# MxxxOVR.net
KiCad netlist of a schematic drawn in EAGLE
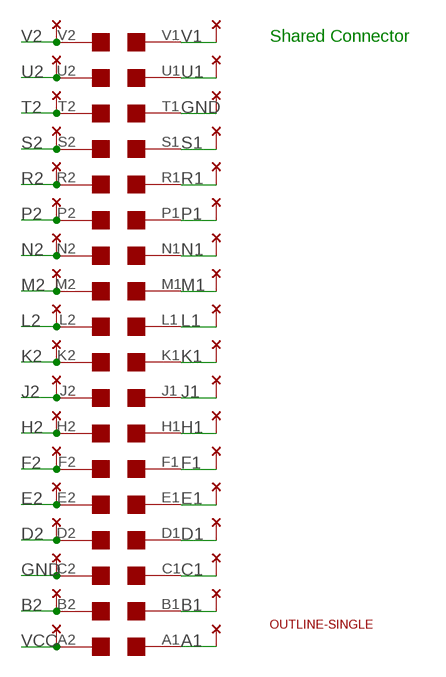
[diagram p0: schematic, sheet 1]
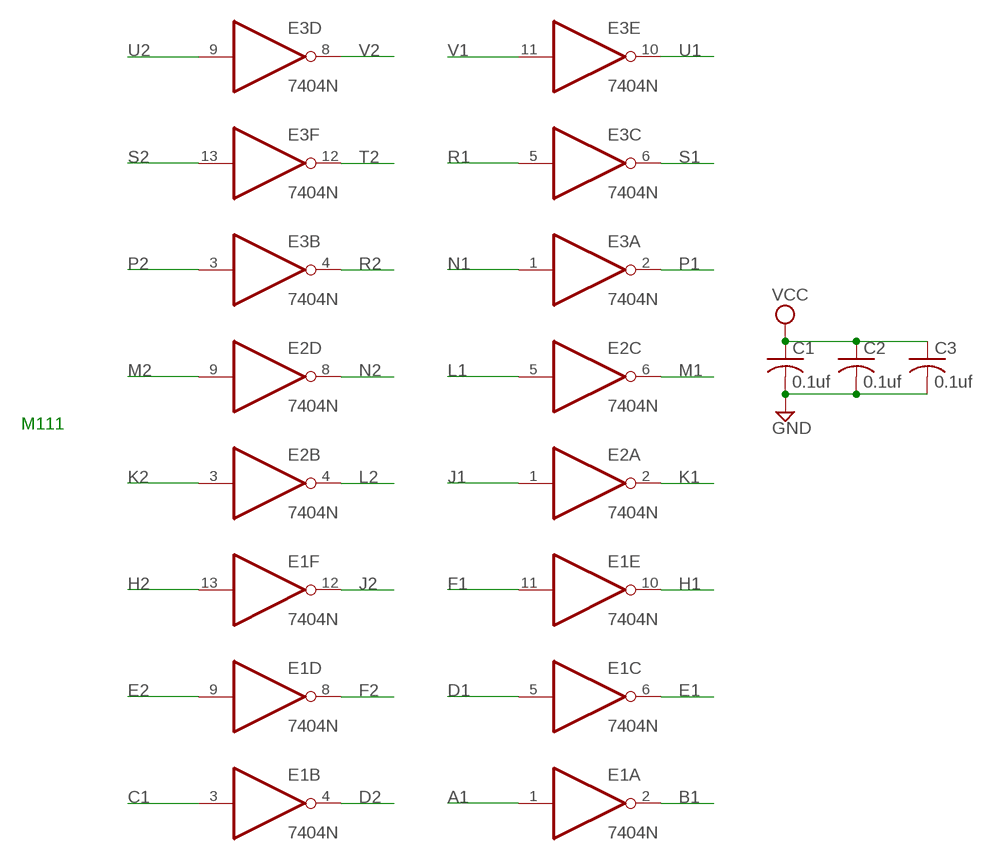
[diagram p1: schematic, sheet 2]
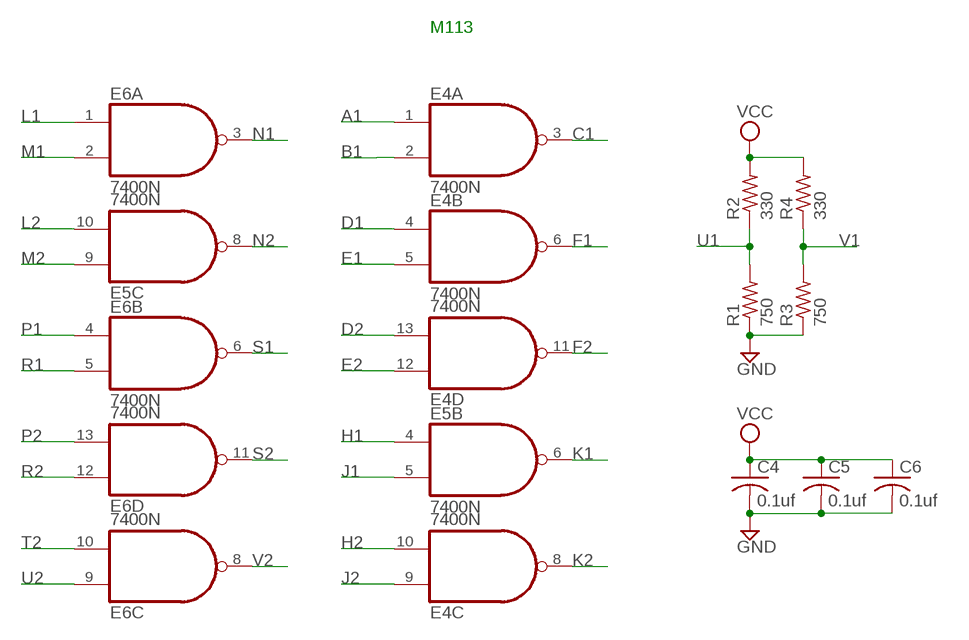
[diagram p2: schematic, sheet 3]
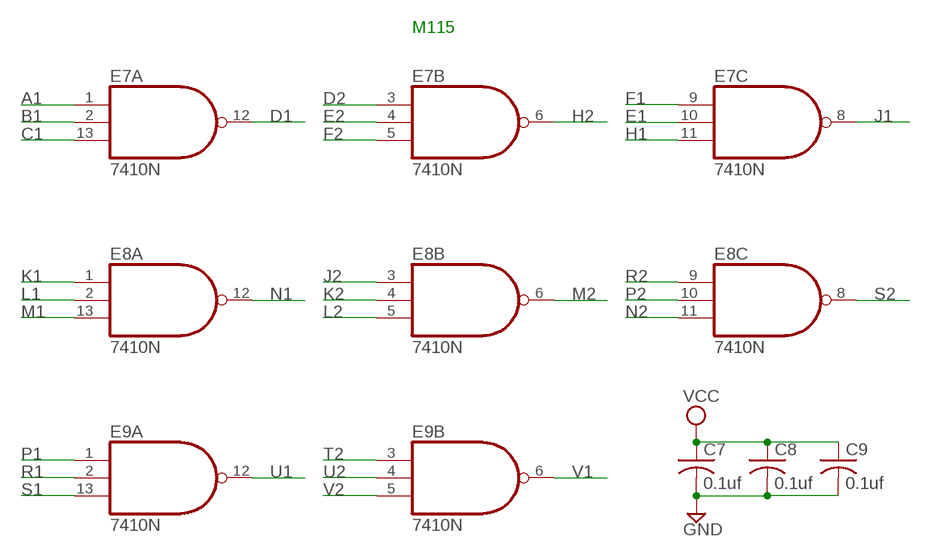
[diagram p3: schematic, sheet 4]
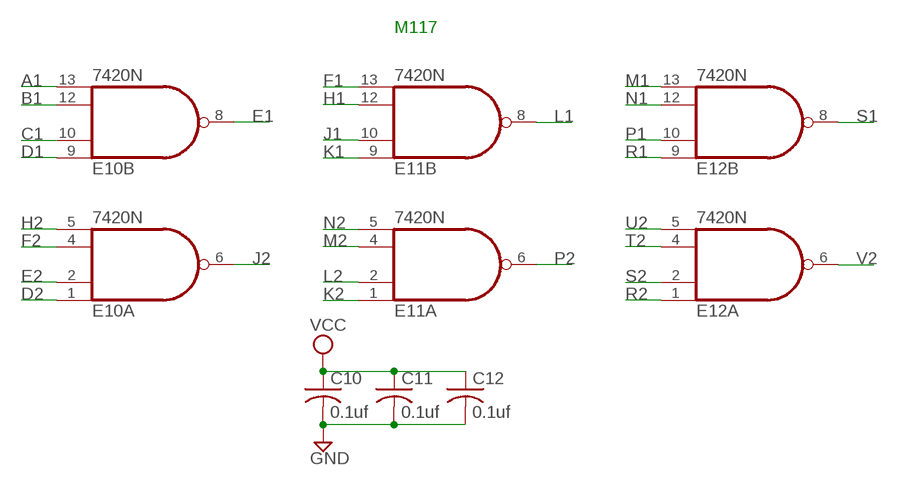
[diagram p4: schematic, sheet 5]
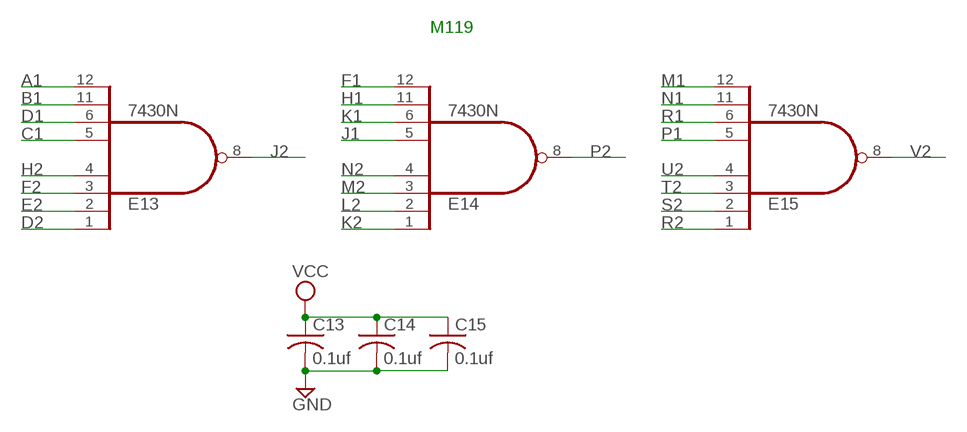
[diagram p5: schematic, sheet 6]

(export (version "E")
  (design (tool "Eeschema 10.0.6"))
  (components
    (comp (ref "C4")
      (value "0.1uf")
      (footprint "eagle-import:C050-025X075")
      (libsource (lib "eagle-import") (part "C-US050-025X075"))
    )
    (comp (ref "C5")
      (value "0.1uf")
      (footprint "eagle-import:C050-025X075")
      (libsource (lib "eagle-import") (part "C-US050-025X075"))
    )
    (comp (ref "C6")
      (value "0.1uf")
      (footprint "eagle-import:C050-025X075")
      (libsource (lib "eagle-import") (part "C-US050-025X075"))
    )
    (comp (ref "E4")
      (value "7400N")
      (footprint "eagle-import:DIL14")
      (libsource (lib "eagle-import") (part "7400N"))
    )
    (comp (ref "E5")
      (value "7400N")
      (footprint "eagle-import:DIL14")
      (libsource (lib "eagle-import") (part "7400N"))
    )
    (comp (ref "E6")
      (value "7400N")
      (footprint "eagle-import:DIL14")
      (libsource (lib "eagle-import") (part "7400N"))
    )
    (comp (ref "R1")
      (value "750")
      (footprint "eagle-import:0207_10")
      (libsource (lib "eagle-import") (part "R-US_0207/10"))
    )
    (comp (ref "R2")
      (value "330")
      (footprint "eagle-import:0207_10")
      (libsource (lib "eagle-import") (part "R-US_0207/10"))
    )
    (comp (ref "R3")
      (value "750")
      (footprint "eagle-import:0207_10")
      (libsource (lib "eagle-import") (part "R-US_0207/10"))
    )
    (comp (ref "R4")
      (value "330")
      (footprint "eagle-import:0207_10")
      (libsource (lib "eagle-import") (part "R-US_0207/10"))
    )
    (comp (ref "U$1")
      (value "EDGE-2CONNECTOR")
      (footprint "eagle-import:EDGE-CON2")
      (libsource (lib "eagle-import") (part "EDGE-2CONNECTOR"))
    )
    (comp (ref "U$4")
      (value "THRU-HOLE2A")
      (footprint "eagle-import:THRU-HOLEA")
      (libsource (lib "eagle-import") (part "THRU-HOLE2A"))
    )
    (comp (ref "U$5")
      (value "OUTLINE-SINGLE")
      (footprint "eagle-import:SINGLE")
      (libsource (lib "eagle-import") (part "OUTLINE-SINGLE"))
    )
    (comp (ref "C13")
      (value "0.1uf")
      (footprint "eagle-import:C050-025X075")
      (libsource (lib "eagle-import") (part "C-US050-025X075"))
    )
    (comp (ref "C14")
      (value "0.1uf")
      (footprint "eagle-import:C050-025X075")
      (libsource (lib "eagle-import") (part "C-US050-025X075"))
    )
    (comp (ref "C15")
      (value "0.1uf")
      (footprint "eagle-import:C050-025X075")
      (libsource (lib "eagle-import") (part "C-US050-025X075"))
    )
    (comp (ref "E13")
      (value "7430N")
      (footprint "eagle-import:DIL14")
      (libsource (lib "eagle-import") (part "7430N"))
    )
    (comp (ref "E14")
      (value "7430N")
      (footprint "eagle-import:DIL14")
      (libsource (lib "eagle-import") (part "7430N"))
    )
    (comp (ref "E15")
      (value "7430N")
      (footprint "eagle-import:DIL14")
      (libsource (lib "eagle-import") (part "7430N"))
    )
    (comp (ref "C1")
      (value "0.1uf")
      (footprint "eagle-import:C050-025X075")
      (libsource (lib "eagle-import") (part "C-US050-025X075"))
    )
    (comp (ref "C2")
      (value "0.1uf")
      (footprint "eagle-import:C050-025X075")
      (libsource (lib "eagle-import") (part "C-US050-025X075"))
    )
    (comp (ref "C3")
      (value "0.1uf")
      (footprint "eagle-import:C050-025X075")
      (libsource (lib "eagle-import") (part "C-US050-025X075"))
    )
    (comp (ref "E1")
      (value "7404N")
      (footprint "eagle-import:DIL14")
      (libsource (lib "eagle-import") (part "7404N"))
    )
    (comp (ref "E2")
      (value "7404N")
      (footprint "eagle-import:DIL14")
      (libsource (lib "eagle-import") (part "7404N"))
    )
    (comp (ref "E3")
      (value "7404N")
      (footprint "eagle-import:DIL14")
      (libsource (lib "eagle-import") (part "7404N"))
    )
    (comp (ref "C10")
      (value "0.1uf")
      (footprint "eagle-import:C050-025X075")
      (libsource (lib "eagle-import") (part "C-US050-025X075"))
    )
    (comp (ref "C11")
      (value "0.1uf")
      (footprint "eagle-import:C050-025X075")
      (libsource (lib "eagle-import") (part "C-US050-025X075"))
    )
    (comp (ref "C12")
      (value "0.1uf")
      (footprint "eagle-import:C050-025X075")
      (libsource (lib "eagle-import") (part "C-US050-025X075"))
    )
    (comp (ref "E10")
      (value "7420N")
      (footprint "eagle-import:DIL14")
      (libsource (lib "eagle-import") (part "7420NS"))
    )
    (comp (ref "E11")
      (value "7420N")
      (footprint "eagle-import:DIL14")
      (libsource (lib "eagle-import") (part "7420NS"))
    )
    (comp (ref "E12")
      (value "7420N")
      (footprint "eagle-import:DIL14")
      (libsource (lib "eagle-import") (part "7420NS"))
    )
    (comp (ref "C7")
      (value "0.1uf")
      (footprint "eagle-import:C050-025X075")
      (libsource (lib "eagle-import") (part "C-US050-025X075"))
    )
    (comp (ref "C8")
      (value "0.1uf")
      (footprint "eagle-import:C050-025X075")
      (libsource (lib "eagle-import") (part "C-US050-025X075"))
    )
    (comp (ref "C9")
      (value "0.1uf")
      (footprint "eagle-import:C050-025X075")
      (libsource (lib "eagle-import") (part "C-US050-025X075"))
    )
    (comp (ref "E7")
      (value "7410N")
      (footprint "eagle-import:DIL14")
      (libsource (lib "eagle-import") (part "7410N"))
    )
    (comp (ref "E8")
      (value "7410N")
      (footprint "eagle-import:DIL14")
      (libsource (lib "eagle-import") (part "7410N"))
    )
    (comp (ref "E9")
      (value "7410N")
      (footprint "eagle-import:DIL14")
      (libsource (lib "eagle-import") (part "7410N"))
    )
  )
  (nets
    (net (code "1") (name "A1") (class "Default")
      (node (ref "E1") (pin "1") (pinfunction "I_1") (pintype "input"))
      (node (ref "E10") (pin "13") (pinfunction "I3_13") (pintype "input"))
      (node (ref "E13") (pin "12") (pinfunction "I7_12") (pintype "input"))
      (node (ref "E4") (pin "1") (pinfunction "I0_1") (pintype "input"))
      (node (ref "E7") (pin "1") (pinfunction "I0_1") (pintype "input"))
      (node (ref "U$1") (pin "A1") (pinfunction "1_A1") (pintype "bidirectional"))
      (node (ref "U$4") (pin "A1") (pinfunction "P$1_A1") (pintype "passive"))
    )
    (net (code "2") (name "B1") (class "Default")
      (node (ref "E1") (pin "2") (pinfunction "O_2") (pintype "output"))
      (node (ref "E10") (pin "12") (pinfunction "I2_12") (pintype "input"))
      (node (ref "E13") (pin "11") (pinfunction "I6_11") (pintype "input"))
      (node (ref "E4") (pin "2") (pinfunction "I1_2") (pintype "input"))
      (node (ref "E7") (pin "2") (pinfunction "I1_2") (pintype "input"))
      (node (ref "U$1") (pin "B1") (pinfunction "1_B1") (pintype "bidirectional"))
      (node (ref "U$4") (pin "B1") (pinfunction "P$1_B1") (pintype "passive"))
    )
    (net (code "3") (name "B2") (class "Default")
      (node (ref "U$1") (pin "B2") (pinfunction "1_B2") (pintype "bidirectional"))
      (node (ref "U$4") (pin "B2") (pinfunction "P$1_B2") (pintype "passive"))
    )
    (net (code "4") (name "C1") (class "Default")
      (node (ref "E1") (pin "3") (pinfunction "I_3") (pintype "input"))
      (node (ref "E10") (pin "10") (pinfunction "I1_10") (pintype "input"))
      (node (ref "E13") (pin "5") (pinfunction "I4_5") (pintype "input"))
      (node (ref "E4") (pin "3") (pinfunction "O_3") (pintype "output"))
      (node (ref "E7") (pin "13") (pinfunction "I2_13") (pintype "input"))
      (node (ref "U$1") (pin "C1") (pinfunction "1_C1") (pintype "bidirectional"))
      (node (ref "U$4") (pin "C1") (pinfunction "P$1_C1") (pintype "passive"))
    )
    (net (code "5") (name "D1") (class "Default")
      (node (ref "E1") (pin "5") (pinfunction "I_5") (pintype "input"))
      (node (ref "E10") (pin "9") (pinfunction "I0_9") (pintype "input"))
      (node (ref "E13") (pin "6") (pinfunction "I5_6") (pintype "input"))
      (node (ref "E4") (pin "4") (pinfunction "I0_4") (pintype "input"))
      (node (ref "E7") (pin "12") (pinfunction "O_12") (pintype "output"))
      (node (ref "U$1") (pin "D1") (pinfunction "1_D1") (pintype "bidirectional"))
      (node (ref "U$4") (pin "D1") (pinfunction "P$1_D1") (pintype "passive"))
    )
    (net (code "6") (name "D2") (class "Default")
      (node (ref "E1") (pin "4") (pinfunction "O_4") (pintype "output"))
      (node (ref "E10") (pin "1") (pinfunction "I0_1") (pintype "input"))
      (node (ref "E13") (pin "1") (pinfunction "I0_1") (pintype "input"))
      (node (ref "E4") (pin "13") (pinfunction "I1_13") (pintype "input"))
      (node (ref "E7") (pin "3") (pinfunction "I0_3") (pintype "input"))
      (node (ref "U$1") (pin "D2") (pinfunction "1_D2") (pintype "bidirectional"))
      (node (ref "U$4") (pin "D2") (pinfunction "P$1_D2") (pintype "passive"))
    )
    (net (code "7") (name "E1") (class "Default")
      (node (ref "E1") (pin "6") (pinfunction "O_6") (pintype "output"))
      (node (ref "E10") (pin "8") (pinfunction "O_8") (pintype "output"))
      (node (ref "E4") (pin "5") (pinfunction "I1_5") (pintype "input"))
      (node (ref "E7") (pin "10") (pinfunction "I1_10") (pintype "input"))
      (node (ref "U$1") (pin "E1") (pinfunction "1_E1") (pintype "bidirectional"))
      (node (ref "U$4") (pin "E1") (pinfunction "P$1_E1") (pintype "passive"))
    )
    (net (code "8") (name "E2") (class "Default")
      (node (ref "E1") (pin "9") (pinfunction "I_9") (pintype "input"))
      (node (ref "E10") (pin "2") (pinfunction "I1_2") (pintype "input"))
      (node (ref "E13") (pin "2") (pinfunction "I1_2") (pintype "input"))
      (node (ref "E4") (pin "12") (pinfunction "I0_12") (pintype "input"))
      (node (ref "E7") (pin "4") (pinfunction "I1_4") (pintype "input"))
      (node (ref "U$1") (pin "E2") (pinfunction "1_E2") (pintype "bidirectional"))
      (node (ref "U$4") (pin "E2") (pinfunction "P$1_E2") (pintype "passive"))
    )
    (net (code "9") (name "F1") (class "Default")
      (node (ref "E1") (pin "11") (pinfunction "I_11") (pintype "input"))
      (node (ref "E11") (pin "13") (pinfunction "I3_13") (pintype "input"))
      (node (ref "E14") (pin "12") (pinfunction "I7_12") (pintype "input"))
      (node (ref "E4") (pin "6") (pinfunction "O_6") (pintype "output"))
      (node (ref "E7") (pin "9") (pinfunction "I0_9") (pintype "input"))
      (node (ref "U$1") (pin "F1") (pinfunction "1_F1") (pintype "bidirectional"))
      (node (ref "U$4") (pin "F1") (pinfunction "P$1_F1") (pintype "passive"))
    )
    (net (code "10") (name "F2") (class "Default")
      (node (ref "E1") (pin "8") (pinfunction "O_8") (pintype "output"))
      (node (ref "E10") (pin "4") (pinfunction "I2_4") (pintype "input"))
      (node (ref "E13") (pin "3") (pinfunction "I2_3") (pintype "input"))
      (node (ref "E4") (pin "11") (pinfunction "O_11") (pintype "output"))
      (node (ref "E7") (pin "5") (pinfunction "I2_5") (pintype "input"))
      (node (ref "U$1") (pin "F2") (pinfunction "1_F2") (pintype "bidirectional"))
      (node (ref "U$4") (pin "F2") (pinfunction "P$1_F2") (pintype "passive"))
    )
    (net (code "11") (name "GND") (class "Default")
      (node (ref "C1") (pin "2") (pinfunction "2_2") (pintype "passive"))
      (node (ref "C10") (pin "2") (pinfunction "2_2") (pintype "passive"))
      (node (ref "C11") (pin "2") (pinfunction "2_2") (pintype "passive"))
      (node (ref "C12") (pin "2") (pinfunction "2_2") (pintype "passive"))
      (node (ref "C13") (pin "2") (pinfunction "2_2") (pintype "passive"))
      (node (ref "C14") (pin "2") (pinfunction "2_2") (pintype "passive"))
      (node (ref "C15") (pin "2") (pinfunction "2_2") (pintype "passive"))
      (node (ref "C2") (pin "2") (pinfunction "2_2") (pintype "passive"))
      (node (ref "C3") (pin "2") (pinfunction "2_2") (pintype "passive"))
      (node (ref "C4") (pin "2") (pinfunction "2_2") (pintype "passive"))
      (node (ref "C5") (pin "2") (pinfunction "2_2") (pintype "passive"))
      (node (ref "C6") (pin "2") (pinfunction "2_2") (pintype "passive"))
      (node (ref "C7") (pin "2") (pinfunction "2_2") (pintype "passive"))
      (node (ref "C8") (pin "2") (pinfunction "2_2") (pintype "passive"))
      (node (ref "C9") (pin "2") (pinfunction "2_2") (pintype "passive"))
      (node (ref "R1") (pin "1") (pinfunction "1_1") (pintype "passive"))
      (node (ref "R3") (pin "1") (pinfunction "1_1") (pintype "passive"))
      (node (ref "U$1") (pin "C2") (pinfunction "1_C2") (pintype "bidirectional"))
      (node (ref "U$1") (pin "T1") (pinfunction "1_T1") (pintype "bidirectional"))
      (node (ref "U$4") (pin "C2") (pinfunction "P$1_C2") (pintype "passive"))
      (node (ref "U$4") (pin "T1") (pinfunction "P$1_T1") (pintype "passive"))
    )
    (net (code "12") (name "H1") (class "Default")
      (node (ref "E1") (pin "10") (pinfunction "O_10") (pintype "output"))
      (node (ref "E11") (pin "12") (pinfunction "I2_12") (pintype "input"))
      (node (ref "E14") (pin "11") (pinfunction "I6_11") (pintype "input"))
      (node (ref "E5") (pin "4") (pinfunction "I0_4") (pintype "input"))
      (node (ref "E7") (pin "11") (pinfunction "I2_11") (pintype "input"))
      (node (ref "U$1") (pin "H1") (pinfunction "1_H1") (pintype "bidirectional"))
      (node (ref "U$4") (pin "H1") (pinfunction "P$1_H1") (pintype "passive"))
    )
    (net (code "13") (name "H2") (class "Default")
      (node (ref "E1") (pin "13") (pinfunction "I_13") (pintype "input"))
      (node (ref "E10") (pin "5") (pinfunction "I3_5") (pintype "input"))
      (node (ref "E13") (pin "4") (pinfunction "I3_4") (pintype "input"))
      (node (ref "E4") (pin "10") (pinfunction "I1_10") (pintype "input"))
      (node (ref "E7") (pin "6") (pinfunction "O_6") (pintype "output"))
      (node (ref "U$1") (pin "H2") (pinfunction "1_H2") (pintype "bidirectional"))
      (node (ref "U$4") (pin "H2") (pinfunction "P$1_H2") (pintype "passive"))
    )
    (net (code "14") (name "J1") (class "Default")
      (node (ref "E11") (pin "10") (pinfunction "I1_10") (pintype "input"))
      (node (ref "E14") (pin "5") (pinfunction "I4_5") (pintype "input"))
      (node (ref "E2") (pin "1") (pinfunction "I_1") (pintype "input"))
      (node (ref "E5") (pin "5") (pinfunction "I1_5") (pintype "input"))
      (node (ref "E7") (pin "8") (pinfunction "O_8") (pintype "output"))
      (node (ref "U$1") (pin "J1") (pinfunction "1_J1") (pintype "bidirectional"))
      (node (ref "U$4") (pin "J1") (pinfunction "P$1_J1") (pintype "passive"))
    )
    (net (code "15") (name "J2") (class "Default")
      (node (ref "E1") (pin "12") (pinfunction "O_12") (pintype "output"))
      (node (ref "E10") (pin "6") (pinfunction "O_6") (pintype "output"))
      (node (ref "E13") (pin "8") (pinfunction "O_8") (pintype "output"))
      (node (ref "E4") (pin "9") (pinfunction "I0_9") (pintype "input"))
      (node (ref "E8") (pin "3") (pinfunction "I0_3") (pintype "input"))
      (node (ref "U$1") (pin "J2") (pinfunction "1_J2") (pintype "bidirectional"))
      (node (ref "U$4") (pin "J2") (pinfunction "P$1_J2") (pintype "passive"))
    )
    (net (code "16") (name "K1") (class "Default")
      (node (ref "E11") (pin "9") (pinfunction "I0_9") (pintype "input"))
      (node (ref "E14") (pin "6") (pinfunction "I5_6") (pintype "input"))
      (node (ref "E2") (pin "2") (pinfunction "O_2") (pintype "output"))
      (node (ref "E5") (pin "6") (pinfunction "O_6") (pintype "output"))
      (node (ref "E8") (pin "1") (pinfunction "I0_1") (pintype "input"))
      (node (ref "U$1") (pin "K1") (pinfunction "1_K1") (pintype "bidirectional"))
      (node (ref "U$4") (pin "K1") (pinfunction "P$1_K1") (pintype "passive"))
    )
    (net (code "17") (name "K2") (class "Default")
      (node (ref "E11") (pin "1") (pinfunction "I0_1") (pintype "input"))
      (node (ref "E14") (pin "1") (pinfunction "I0_1") (pintype "input"))
      (node (ref "E2") (pin "3") (pinfunction "I_3") (pintype "input"))
      (node (ref "E4") (pin "8") (pinfunction "O_8") (pintype "output"))
      (node (ref "E8") (pin "4") (pinfunction "I1_4") (pintype "input"))
      (node (ref "U$1") (pin "K2") (pinfunction "1_K2") (pintype "bidirectional"))
      (node (ref "U$4") (pin "K2") (pinfunction "P$1_K2") (pintype "passive"))
    )
    (net (code "18") (name "L1") (class "Default")
      (node (ref "E11") (pin "8") (pinfunction "O_8") (pintype "output"))
      (node (ref "E2") (pin "5") (pinfunction "I_5") (pintype "input"))
      (node (ref "E6") (pin "1") (pinfunction "I0_1") (pintype "input"))
      (node (ref "E8") (pin "2") (pinfunction "I1_2") (pintype "input"))
      (node (ref "U$1") (pin "L1") (pinfunction "1_L1") (pintype "bidirectional"))
      (node (ref "U$4") (pin "L1") (pinfunction "P$1_L1") (pintype "passive"))
    )
    (net (code "19") (name "L2") (class "Default")
      (node (ref "E11") (pin "2") (pinfunction "I1_2") (pintype "input"))
      (node (ref "E14") (pin "2") (pinfunction "I1_2") (pintype "input"))
      (node (ref "E2") (pin "4") (pinfunction "O_4") (pintype "output"))
      (node (ref "E5") (pin "10") (pinfunction "I1_10") (pintype "input"))
      (node (ref "E8") (pin "5") (pinfunction "I2_5") (pintype "input"))
      (node (ref "U$1") (pin "L2") (pinfunction "1_L2") (pintype "bidirectional"))
      (node (ref "U$4") (pin "L2") (pinfunction "P$1_L2") (pintype "passive"))
    )
    (net (code "20") (name "M1") (class "Default")
      (node (ref "E12") (pin "13") (pinfunction "I3_13") (pintype "input"))
      (node (ref "E15") (pin "12") (pinfunction "I7_12") (pintype "input"))
      (node (ref "E2") (pin "6") (pinfunction "O_6") (pintype "output"))
      (node (ref "E6") (pin "2") (pinfunction "I1_2") (pintype "input"))
      (node (ref "E8") (pin "13") (pinfunction "I2_13") (pintype "input"))
      (node (ref "U$1") (pin "M1") (pinfunction "1_M1") (pintype "bidirectional"))
      (node (ref "U$4") (pin "M1") (pinfunction "P$1_M1") (pintype "passive"))
    )
    (net (code "21") (name "M2") (class "Default")
      (node (ref "E11") (pin "4") (pinfunction "I2_4") (pintype "input"))
      (node (ref "E14") (pin "3") (pinfunction "I2_3") (pintype "input"))
      (node (ref "E2") (pin "9") (pinfunction "I_9") (pintype "input"))
      (node (ref "E5") (pin "9") (pinfunction "I0_9") (pintype "input"))
      (node (ref "E8") (pin "6") (pinfunction "O_6") (pintype "output"))
      (node (ref "U$1") (pin "M2") (pinfunction "1_M2") (pintype "bidirectional"))
      (node (ref "U$4") (pin "M2") (pinfunction "P$1_M2") (pintype "passive"))
    )
    (net (code "22") (name "N1") (class "Default")
      (node (ref "E12") (pin "12") (pinfunction "I2_12") (pintype "input"))
      (node (ref "E15") (pin "11") (pinfunction "I6_11") (pintype "input"))
      (node (ref "E3") (pin "1") (pinfunction "I_1") (pintype "input"))
      (node (ref "E6") (pin "3") (pinfunction "O_3") (pintype "output"))
      (node (ref "E8") (pin "12") (pinfunction "O_12") (pintype "output"))
      (node (ref "U$1") (pin "N1") (pinfunction "1_N1") (pintype "bidirectional"))
      (node (ref "U$4") (pin "N1") (pinfunction "P$1_N1") (pintype "passive"))
    )
    (net (code "23") (name "N2") (class "Default")
      (node (ref "E11") (pin "5") (pinfunction "I3_5") (pintype "input"))
      (node (ref "E14") (pin "4") (pinfunction "I3_4") (pintype "input"))
      (node (ref "E2") (pin "8") (pinfunction "O_8") (pintype "output"))
      (node (ref "E5") (pin "8") (pinfunction "O_8") (pintype "output"))
      (node (ref "E8") (pin "11") (pinfunction "I2_11") (pintype "input"))
      (node (ref "U$1") (pin "N2") (pinfunction "1_N2") (pintype "bidirectional"))
      (node (ref "U$4") (pin "N2") (pinfunction "P$1_N2") (pintype "passive"))
    )
    (net (code "24") (name "P1") (class "Default")
      (node (ref "E12") (pin "10") (pinfunction "I1_10") (pintype "input"))
      (node (ref "E15") (pin "5") (pinfunction "I4_5") (pintype "input"))
      (node (ref "E3") (pin "2") (pinfunction "O_2") (pintype "output"))
      (node (ref "E6") (pin "4") (pinfunction "I0_4") (pintype "input"))
      (node (ref "E9") (pin "1") (pinfunction "I0_1") (pintype "input"))
      (node (ref "U$1") (pin "P1") (pinfunction "1_P1") (pintype "bidirectional"))
      (node (ref "U$4") (pin "P1") (pinfunction "P$1_P1") (pintype "passive"))
    )
    (net (code "25") (name "P2") (class "Default")
      (node (ref "E11") (pin "6") (pinfunction "O_6") (pintype "output"))
      (node (ref "E14") (pin "8") (pinfunction "O_8") (pintype "output"))
      (node (ref "E3") (pin "3") (pinfunction "I_3") (pintype "input"))
      (node (ref "E6") (pin "13") (pinfunction "I1_13") (pintype "input"))
      (node (ref "E8") (pin "10") (pinfunction "I1_10") (pintype "input"))
      (node (ref "U$1") (pin "P2") (pinfunction "1_P2") (pintype "bidirectional"))
      (node (ref "U$4") (pin "P2") (pinfunction "P$1_P2") (pintype "passive"))
    )
    (net (code "26") (name "R1") (class "Default")
      (node (ref "E12") (pin "9") (pinfunction "I0_9") (pintype "input"))
      (node (ref "E15") (pin "6") (pinfunction "I5_6") (pintype "input"))
      (node (ref "E3") (pin "5") (pinfunction "I_5") (pintype "input"))
      (node (ref "E6") (pin "5") (pinfunction "I1_5") (pintype "input"))
      (node (ref "E9") (pin "2") (pinfunction "I1_2") (pintype "input"))
      (node (ref "U$1") (pin "R1") (pinfunction "1_R1") (pintype "bidirectional"))
      (node (ref "U$4") (pin "R1") (pinfunction "P$1_R1") (pintype "passive"))
    )
    (net (code "27") (name "R2") (class "Default")
      (node (ref "E12") (pin "1") (pinfunction "I0_1") (pintype "input"))
      (node (ref "E15") (pin "1") (pinfunction "I0_1") (pintype "input"))
      (node (ref "E3") (pin "4") (pinfunction "O_4") (pintype "output"))
      (node (ref "E6") (pin "12") (pinfunction "I0_12") (pintype "input"))
      (node (ref "E8") (pin "9") (pinfunction "I0_9") (pintype "input"))
      (node (ref "U$1") (pin "R2") (pinfunction "1_R2") (pintype "bidirectional"))
      (node (ref "U$4") (pin "R2") (pinfunction "P$1_R2") (pintype "passive"))
    )
    (net (code "28") (name "S1") (class "Default")
      (node (ref "E12") (pin "8") (pinfunction "O_8") (pintype "output"))
      (node (ref "E3") (pin "6") (pinfunction "O_6") (pintype "output"))
      (node (ref "E6") (pin "6") (pinfunction "O_6") (pintype "output"))
      (node (ref "E9") (pin "13") (pinfunction "I2_13") (pintype "input"))
      (node (ref "U$1") (pin "S1") (pinfunction "1_S1") (pintype "bidirectional"))
      (node (ref "U$4") (pin "S1") (pinfunction "P$1_S1") (pintype "passive"))
    )
    (net (code "29") (name "S2") (class "Default")
      (node (ref "E12") (pin "2") (pinfunction "I1_2") (pintype "input"))
      (node (ref "E15") (pin "2") (pinfunction "I1_2") (pintype "input"))
      (node (ref "E3") (pin "13") (pinfunction "I_13") (pintype "input"))
      (node (ref "E6") (pin "11") (pinfunction "O_11") (pintype "output"))
      (node (ref "E8") (pin "8") (pinfunction "O_8") (pintype "output"))
      (node (ref "U$1") (pin "S2") (pinfunction "1_S2") (pintype "bidirectional"))
      (node (ref "U$4") (pin "S2") (pinfunction "P$1_S2") (pintype "passive"))
    )
    (net (code "30") (name "T2") (class "Default")
      (node (ref "E12") (pin "4") (pinfunction "I2_4") (pintype "input"))
      (node (ref "E15") (pin "3") (pinfunction "I2_3") (pintype "input"))
      (node (ref "E3") (pin "12") (pinfunction "O_12") (pintype "output"))
      (node (ref "E6") (pin "10") (pinfunction "I1_10") (pintype "input"))
      (node (ref "E9") (pin "3") (pinfunction "I0_3") (pintype "input"))
      (node (ref "U$1") (pin "T2") (pinfunction "1_T2") (pintype "bidirectional"))
      (node (ref "U$4") (pin "T2") (pinfunction "P$1_T2") (pintype "passive"))
    )
    (net (code "31") (name "U1") (class "Default")
      (node (ref "E3") (pin "10") (pinfunction "O_10") (pintype "output"))
      (node (ref "E9") (pin "12") (pinfunction "O_12") (pintype "output"))
      (node (ref "R1") (pin "2") (pinfunction "2_2") (pintype "passive"))
      (node (ref "R2") (pin "1") (pinfunction "1_1") (pintype "passive"))
      (node (ref "U$1") (pin "U1") (pinfunction "1_U1") (pintype "bidirectional"))
      (node (ref "U$4") (pin "U1") (pinfunction "P$1_U1") (pintype "passive"))
    )
    (net (code "32") (name "U2") (class "Default")
      (node (ref "E12") (pin "5") (pinfunction "I3_5") (pintype "input"))
      (node (ref "E15") (pin "4") (pinfunction "I3_4") (pintype "input"))
      (node (ref "E3") (pin "9") (pinfunction "I_9") (pintype "input"))
      (node (ref "E6") (pin "9") (pinfunction "I0_9") (pintype "input"))
      (node (ref "E9") (pin "4") (pinfunction "I1_4") (pintype "input"))
      (node (ref "U$1") (pin "U2") (pinfunction "1_U2") (pintype "bidirectional"))
      (node (ref "U$4") (pin "U2") (pinfunction "P$1_U2") (pintype "passive"))
    )
    (net (code "33") (name "V1") (class "Default")
      (node (ref "E3") (pin "11") (pinfunction "I_11") (pintype "input"))
      (node (ref "E9") (pin "6") (pinfunction "O_6") (pintype "output"))
      (node (ref "R3") (pin "2") (pinfunction "2_2") (pintype "passive"))
      (node (ref "R4") (pin "1") (pinfunction "1_1") (pintype "passive"))
      (node (ref "U$1") (pin "V1") (pinfunction "1_V1") (pintype "bidirectional"))
      (node (ref "U$4") (pin "V1") (pinfunction "P$1_V1") (pintype "passive"))
    )
    (net (code "34") (name "V2") (class "Default")
      (node (ref "E12") (pin "6") (pinfunction "O_6") (pintype "output"))
      (node (ref "E15") (pin "8") (pinfunction "O_8") (pintype "output"))
      (node (ref "E3") (pin "8") (pinfunction "O_8") (pintype "output"))
      (node (ref "E6") (pin "8") (pinfunction "O_8") (pintype "output"))
      (node (ref "E9") (pin "5") (pinfunction "I2_5") (pintype "input"))
      (node (ref "U$1") (pin "V2") (pinfunction "1_V2") (pintype "bidirectional"))
      (node (ref "U$4") (pin "V2") (pinfunction "P$1_V2") (pintype "passive"))
    )
    (net (code "35") (name "VCC") (class "Default")
      (node (ref "C1") (pin "1") (pinfunction "1_1") (pintype "passive"))
      (node (ref "C10") (pin "1") (pinfunction "1_1") (pintype "passive"))
      (node (ref "C11") (pin "1") (pinfunction "1_1") (pintype "passive"))
      (node (ref "C12") (pin "1") (pinfunction "1_1") (pintype "passive"))
      (node (ref "C13") (pin "1") (pinfunction "1_1") (pintype "passive"))
      (node (ref "C14") (pin "1") (pinfunction "1_1") (pintype "passive"))
      (node (ref "C15") (pin "1") (pinfunction "1_1") (pintype "passive"))
      (node (ref "C2") (pin "1") (pinfunction "1_1") (pintype "passive"))
      (node (ref "C3") (pin "1") (pinfunction "1_1") (pintype "passive"))
      (node (ref "C4") (pin "1") (pinfunction "1_1") (pintype "passive"))
      (node (ref "C5") (pin "1") (pinfunction "1_1") (pintype "passive"))
      (node (ref "C6") (pin "1") (pinfunction "1_1") (pintype "passive"))
      (node (ref "C7") (pin "1") (pinfunction "1_1") (pintype "passive"))
      (node (ref "C8") (pin "1") (pinfunction "1_1") (pintype "passive"))
      (node (ref "C9") (pin "1") (pinfunction "1_1") (pintype "passive"))
      (node (ref "R2") (pin "2") (pinfunction "2_2") (pintype "passive"))
      (node (ref "R4") (pin "2") (pinfunction "2_2") (pintype "passive"))
      (node (ref "U$1") (pin "A2") (pinfunction "1_A2") (pintype "bidirectional"))
      (node (ref "U$4") (pin "A2") (pinfunction "P$1_A2") (pintype "passive"))
    )
  )
)
